# Slider.net
KiCad netlist of a schematic drawn in EAGLE
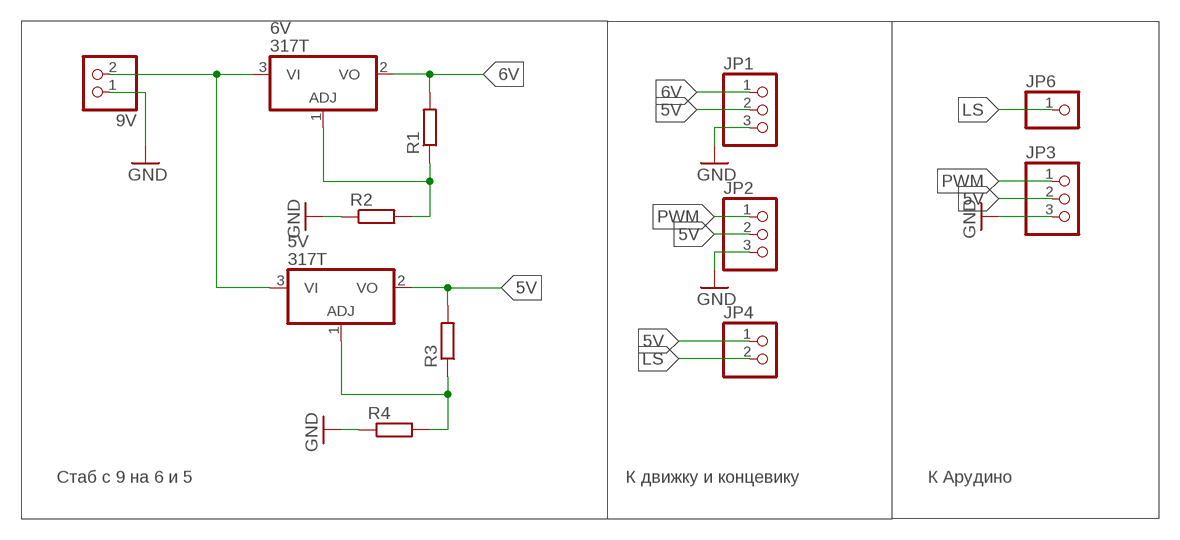
[diagram p0: schematic, sheet 1]

(export (version "E")
  (design (tool "Eeschema 10.0.6"))
  (components
    (comp (ref "5V")
      (value "317T")
      (footprint "eagle-import:TO220H")
      (libsource (lib "eagle-import") (part "317T"))
    )
    (comp (ref "6V")
      (value "317T")
      (footprint "eagle-import:TO220H")
      (libsource (lib "eagle-import") (part "317T"))
    )
    (comp (ref "9V")
      (value "PINHD-1X2")
      (footprint "eagle-import:1X02")
      (libsource (lib "eagle-import") (part "PINHD-1X2"))
    )
    (comp (ref "JP1")
      (value "PINHD-1X3")
      (footprint "eagle-import:1X03")
      (libsource (lib "eagle-import") (part "PINHD-1X3"))
    )
    (comp (ref "JP2")
      (value "PINHD-1X3")
      (footprint "eagle-import:1X03")
      (libsource (lib "eagle-import") (part "PINHD-1X3"))
    )
    (comp (ref "JP3")
      (value "PINHD-1X3")
      (footprint "eagle-import:1X03")
      (libsource (lib "eagle-import") (part "PINHD-1X3"))
    )
    (comp (ref "JP4")
      (value "PINHD-1X2")
      (footprint "eagle-import:1X02")
      (libsource (lib "eagle-import") (part "PINHD-1X2"))
    )
    (comp (ref "JP6")
      (value "PINHD-1X1")
      (footprint "eagle-import:1X01")
      (libsource (lib "eagle-import") (part "PINHD-1X1"))
    )
    (comp (ref "R1")
      (value "R-EU_R0805")
      (footprint "eagle-import:R0805")
      (libsource (lib "eagle-import") (part "R-EU_R0805"))
    )
    (comp (ref "R2")
      (value "R-EU_R0805")
      (footprint "eagle-import:R0805")
      (libsource (lib "eagle-import") (part "R-EU_R0805"))
    )
    (comp (ref "R3")
      (value "R-EU_R0805")
      (footprint "eagle-import:R0805")
      (libsource (lib "eagle-import") (part "R-EU_R0805"))
    )
    (comp (ref "R4")
      (value "R-EU_R0805")
      (footprint "eagle-import:R0805")
      (libsource (lib "eagle-import") (part "R-EU_R0805"))
    )
  )
  (nets
    (net (code "1") (name "5V") (class "Default")
      (node (ref "5V") (pin "2") (pinfunction "VO_2") (pintype "passive"))
      (node (ref "JP1") (pin "2") (pinfunction "2_2") (pintype "passive"))
      (node (ref "JP2") (pin "2") (pinfunction "2_2") (pintype "passive"))
      (node (ref "JP3") (pin "2") (pinfunction "2_2") (pintype "passive"))
      (node (ref "JP4") (pin "1") (pinfunction "1_1") (pintype "passive"))
      (node (ref "R3") (pin "2") (pinfunction "2_2") (pintype "passive"))
    )
    (net (code "2") (name "6V") (class "Default")
      (node (ref "6V") (pin "2") (pinfunction "VO_2") (pintype "passive"))
      (node (ref "JP1") (pin "1") (pinfunction "1_1") (pintype "passive"))
      (node (ref "R1") (pin "2") (pinfunction "2_2") (pintype "passive"))
    )
    (net (code "3") (name "GND") (class "Default")
      (node (ref "9V") (pin "1") (pinfunction "1_1") (pintype "passive"))
      (node (ref "JP1") (pin "3") (pinfunction "3_3") (pintype "passive"))
      (node (ref "JP2") (pin "3") (pinfunction "3_3") (pintype "passive"))
      (node (ref "JP3") (pin "3") (pinfunction "3_3") (pintype "passive"))
      (node (ref "R2") (pin "1") (pinfunction "1_1") (pintype "passive"))
      (node (ref "R4") (pin "1") (pinfunction "1_1") (pintype "passive"))
    )
    (net (code "4") (name "LS") (class "Default")
      (node (ref "JP4") (pin "2") (pinfunction "2_2") (pintype "passive"))
      (node (ref "JP6") (pin "1") (pinfunction "1_1") (pintype "passive"))
    )
    (net (code "5") (name "Net-(5V-ADJ)") (class "Default")
      (node (ref "5V") (pin "1") (pinfunction "ADJ_1") (pintype "input"))
      (node (ref "R3") (pin "1") (pinfunction "1_1") (pintype "passive"))
      (node (ref "R4") (pin "2") (pinfunction "2_2") (pintype "passive"))
    )
    (net (code "6") (name "Net-(5V-VI)") (class "Default")
      (node (ref "5V") (pin "3") (pinfunction "VI_3") (pintype "input"))
      (node (ref "6V") (pin "3") (pinfunction "VI_3") (pintype "input"))
      (node (ref "9V") (pin "2") (pinfunction "2_2") (pintype "passive"))
    )
    (net (code "7") (name "Net-(6V-ADJ)") (class "Default")
      (node (ref "6V") (pin "1") (pinfunction "ADJ_1") (pintype "input"))
      (node (ref "R1") (pin "1") (pinfunction "1_1") (pintype "passive"))
      (node (ref "R2") (pin "2") (pinfunction "2_2") (pintype "passive"))
    )
    (net (code "8") (name "PWM") (class "Default")
      (node (ref "JP2") (pin "1") (pinfunction "1_1") (pintype "passive"))
      (node (ref "JP3") (pin "1") (pinfunction "1_1") (pintype "passive"))
    )
  )
)
